# Sensor.net
KiCad netlist of a schematic drawn in Altium Designer
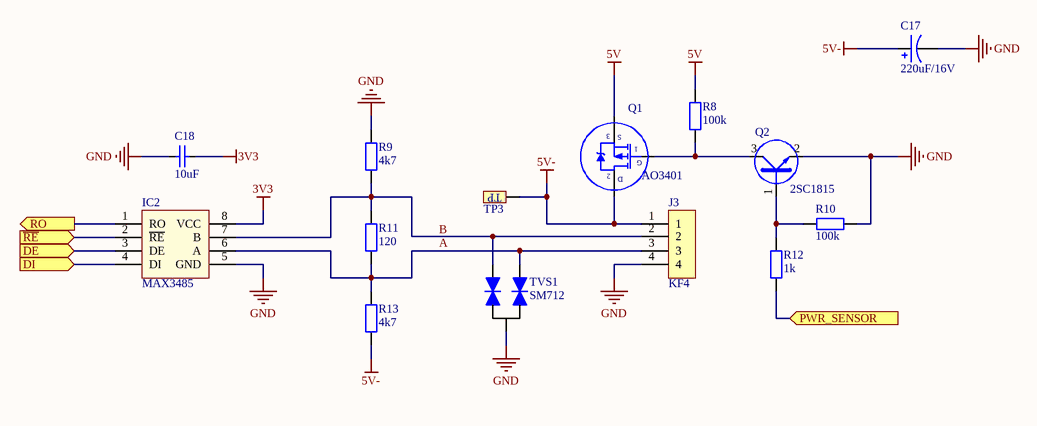
[diagram p0: Sensor.SchDoc]

(export (version "E")
  (design (tool "Eeschema 10.0.6"))
  (components
    (comp (ref "C17")
      (value "220uF/16V")
      (footprint "C5mm")
      (description "Polarized Capacitor (Axial)")
      (fields (field (name "PUBLISHER") "Altium Limited"))
      (libsource (lib "My Library") (part "Cap Pol"))
    )
    (comp (ref "C18")
      (value "10uF")
      (footprint "CAP_0805")
      (description "Capacitor")
      (fields (field (name "PUBLISHER") "Altium Limited"))
      (libsource (lib "My Library") (part "CapSMD"))
    )
    (comp (ref "IC2")
      (value "MAX3485")
      (footprint "SO-8")
      (description "RS232 - RS485 (Same sn75176)")
      (libsource (lib "My Library") (part "MAX485"))
    )
    (comp (ref "J3")
      (value "KF4")
      (footprint "KF4-5.08")
      (fields
        (field (name "MANUFACTURER") "Würth Elektronik eiSos GmbH")
        (field (name "PARTNO") "691133710004")
        (field (name "CREATED BY") "Baojun Chen")
      )
      (libsource (lib "My Library") (part "KF4"))
    )
    (comp (ref "Q1")
      (value "AO3401")
      (footprint "SOT23A")
      (description "30V 5.8A P-Channel MOSFET")
      (libsource (lib "My Library") (part "MOSFET_P"))
    )
    (comp (ref "Q2")
      (value "2SC1815")
      (footprint "SOT23D")
      (description "NPN 600mW, ECB")
      (libsource (lib "My Library") (part "C1815"))
    )
    (comp (ref "R8")
      (value "100k")
      (footprint "RES-SMD-0805")
      (description "Resistor SMD")
      (fields
        (field (name "MANUFACTURER") "Generic Components")
        (field (name "PUBLISHER") "Altium Hobart Technology Centre")
      )
      (libsource (lib "My Library") (part "Resistor - SMD"))
    )
    (comp (ref "R9")
      (value "4k7")
      (footprint "RES-SMD-0805")
      (description "Resistor SMD")
      (fields
        (field (name "MANUFACTURER") "Generic Components")
        (field (name "PUBLISHER") "Altium Hobart Technology Centre")
      )
      (libsource (lib "My Library") (part "Resistor - SMD"))
    )
    (comp (ref "R10")
      (value "100k")
      (footprint "RES-SMD-0805")
      (description "Resistor SMD")
      (fields
        (field (name "MANUFACTURER") "Generic Components")
        (field (name "PUBLISHER") "Altium Hobart Technology Centre")
      )
      (libsource (lib "My Library") (part "Resistor - SMD"))
    )
    (comp (ref "R11")
      (value "120")
      (footprint "RES-SMD-0805")
      (description "Resistor SMD")
      (fields
        (field (name "MANUFACTURER") "Generic Components")
        (field (name "PUBLISHER") "Altium Hobart Technology Centre")
      )
      (libsource (lib "My Library") (part "Resistor - SMD"))
    )
    (comp (ref "R12")
      (value "1k")
      (footprint "RES-SMD-0805")
      (description "Resistor SMD")
      (fields
        (field (name "MANUFACTURER") "Generic Components")
        (field (name "PUBLISHER") "Altium Hobart Technology Centre")
      )
      (libsource (lib "My Library") (part "Resistor - SMD"))
    )
    (comp (ref "R13")
      (value "4k7")
      (footprint "RES-SMD-0805")
      (description "Resistor SMD")
      (fields
        (field (name "MANUFACTURER") "Generic Components")
        (field (name "PUBLISHER") "Altium Hobart Technology Centre")
      )
      (libsource (lib "My Library") (part "Resistor - SMD"))
    )
    (comp (ref "TP3")
      (value "Test Point")
      (footprint "TP_SMD")
      (description "CONNECT 1")
      (libsource (lib "My Library") (part "TP"))
    )
    (comp (ref "TVS1")
      (value "SM712")
      (footprint "SOT23")
      (description "BAV70")
      (libsource (lib "My Library") (part "BAV70"))
    )
  )
  (nets
    (net (code "1") (name "/A") (class "Default")
      (node (ref "IC2") (pin "6") (pinfunction "A_6") (pintype "passive"))
      (node (ref "J3") (pin "3") (pinfunction "3_3") (pintype "passive"))
      (node (ref "R11") (pin "1") (pinfunction "1_1") (pintype "passive"))
      (node (ref "R13") (pin "2") (pinfunction "2_2") (pintype "passive"))
      (node (ref "TVS1") (pin "1") (pinfunction "A_1") (pintype "passive"))
    )
    (net (code "3") (name "/DE") (class "Default")
      (node (ref "IC2") (pin "3") (pinfunction "DE_3") (pintype "passive"))
    )
    (net (code "4") (name "/DI") (class "Default")
      (node (ref "IC2") (pin "4") (pinfunction "DI_4") (pintype "passive"))
    )
    (net (code "5") (name "/PWR_SENSOR") (class "Default")
      (node (ref "R12") (pin "2") (pinfunction "2_2") (pintype "passive"))
    )
    (net (code "6") (name "/RO") (class "Default")
      (node (ref "IC2") (pin "1") (pinfunction "RO_1") (pintype "passive"))
    )
    (net (code "7") (name "/~{RE}") (class "Default")
      (node (ref "IC2") (pin "2") (pinfunction "~{RE}_2") (pintype "passive"))
    )
    (net (code "8") (name "3V3") (class "Default")
      (node (ref "C18") (pin "2") (pinfunction "2_2") (pintype "passive"))
      (node (ref "IC2") (pin "8") (pinfunction "VCC_8") (pintype "passive"))
    )
    (net (code "9") (name "5V") (class "Default")
      (node (ref "Q1") (pin "3") (pinfunction "S_3") (pintype "passive"))
      (node (ref "R8") (pin "1") (pinfunction "1_1") (pintype "passive"))
    )
    (net (code "10") (name "5V-") (class "Default")
      (node (ref "C17") (pin "1") (pinfunction "1_1") (pintype "passive"))
      (node (ref "J3") (pin "1") (pinfunction "1_1") (pintype "passive"))
      (node (ref "Q1") (pin "2") (pinfunction "D_2") (pintype "passive"))
      (node (ref "R13") (pin "1") (pinfunction "1_1") (pintype "passive"))
      (node (ref "TP3") (pin "1") (pinfunction "0_1") (pintype "passive"))
    )
    (net (code "11") (name "GND") (class "Default")
      (node (ref "C17") (pin "2") (pinfunction "2_2") (pintype "passive"))
      (node (ref "C18") (pin "1") (pinfunction "1_1") (pintype "passive"))
      (node (ref "IC2") (pin "5") (pinfunction "GND_5") (pintype "passive"))
      (node (ref "J3") (pin "4") (pinfunction "4_4") (pintype "passive"))
      (node (ref "Q2") (pin "2") (pinfunction "E_2") (pintype "passive"))
      (node (ref "R10") (pin "2") (pinfunction "2_2") (pintype "passive"))
      (node (ref "R9") (pin "2") (pinfunction "2_2") (pintype "passive"))
      (node (ref "TVS1") (pin "3") (pinfunction "K_3") (pintype "passive"))
    )
    (net (code "12") (name "Net-(IC2-B)") (class "Default")
      (node (ref "IC2") (pin "7") (pinfunction "B_7") (pintype "passive"))
      (node (ref "J3") (pin "2") (pinfunction "2_2") (pintype "passive"))
      (node (ref "R11") (pin "2") (pinfunction "2_2") (pintype "passive"))
      (node (ref "R9") (pin "1") (pinfunction "1_1") (pintype "passive"))
      (node (ref "TVS1") (pin "2") (pinfunction "A_2") (pintype "passive"))
    )
    (net (code "13") (name "Net-(Q1-G)") (class "Default")
      (node (ref "Q1") (pin "1") (pinfunction "G_1") (pintype "passive"))
      (node (ref "Q2") (pin "3") (pinfunction "C_3") (pintype "passive"))
      (node (ref "R8") (pin "2") (pinfunction "2_2") (pintype "passive"))
    )
    (net (code "14") (name "Net-(Q2-B)") (class "Default")
      (node (ref "Q2") (pin "1") (pinfunction "B_1") (pintype "passive"))
      (node (ref "R10") (pin "1") (pinfunction "1_1") (pintype "passive"))
      (node (ref "R12") (pin "1") (pinfunction "1_1") (pintype "passive"))
    )
  )
)
